# DoorLockShield.net
KiCad netlist of a schematic drawn in EAGLE
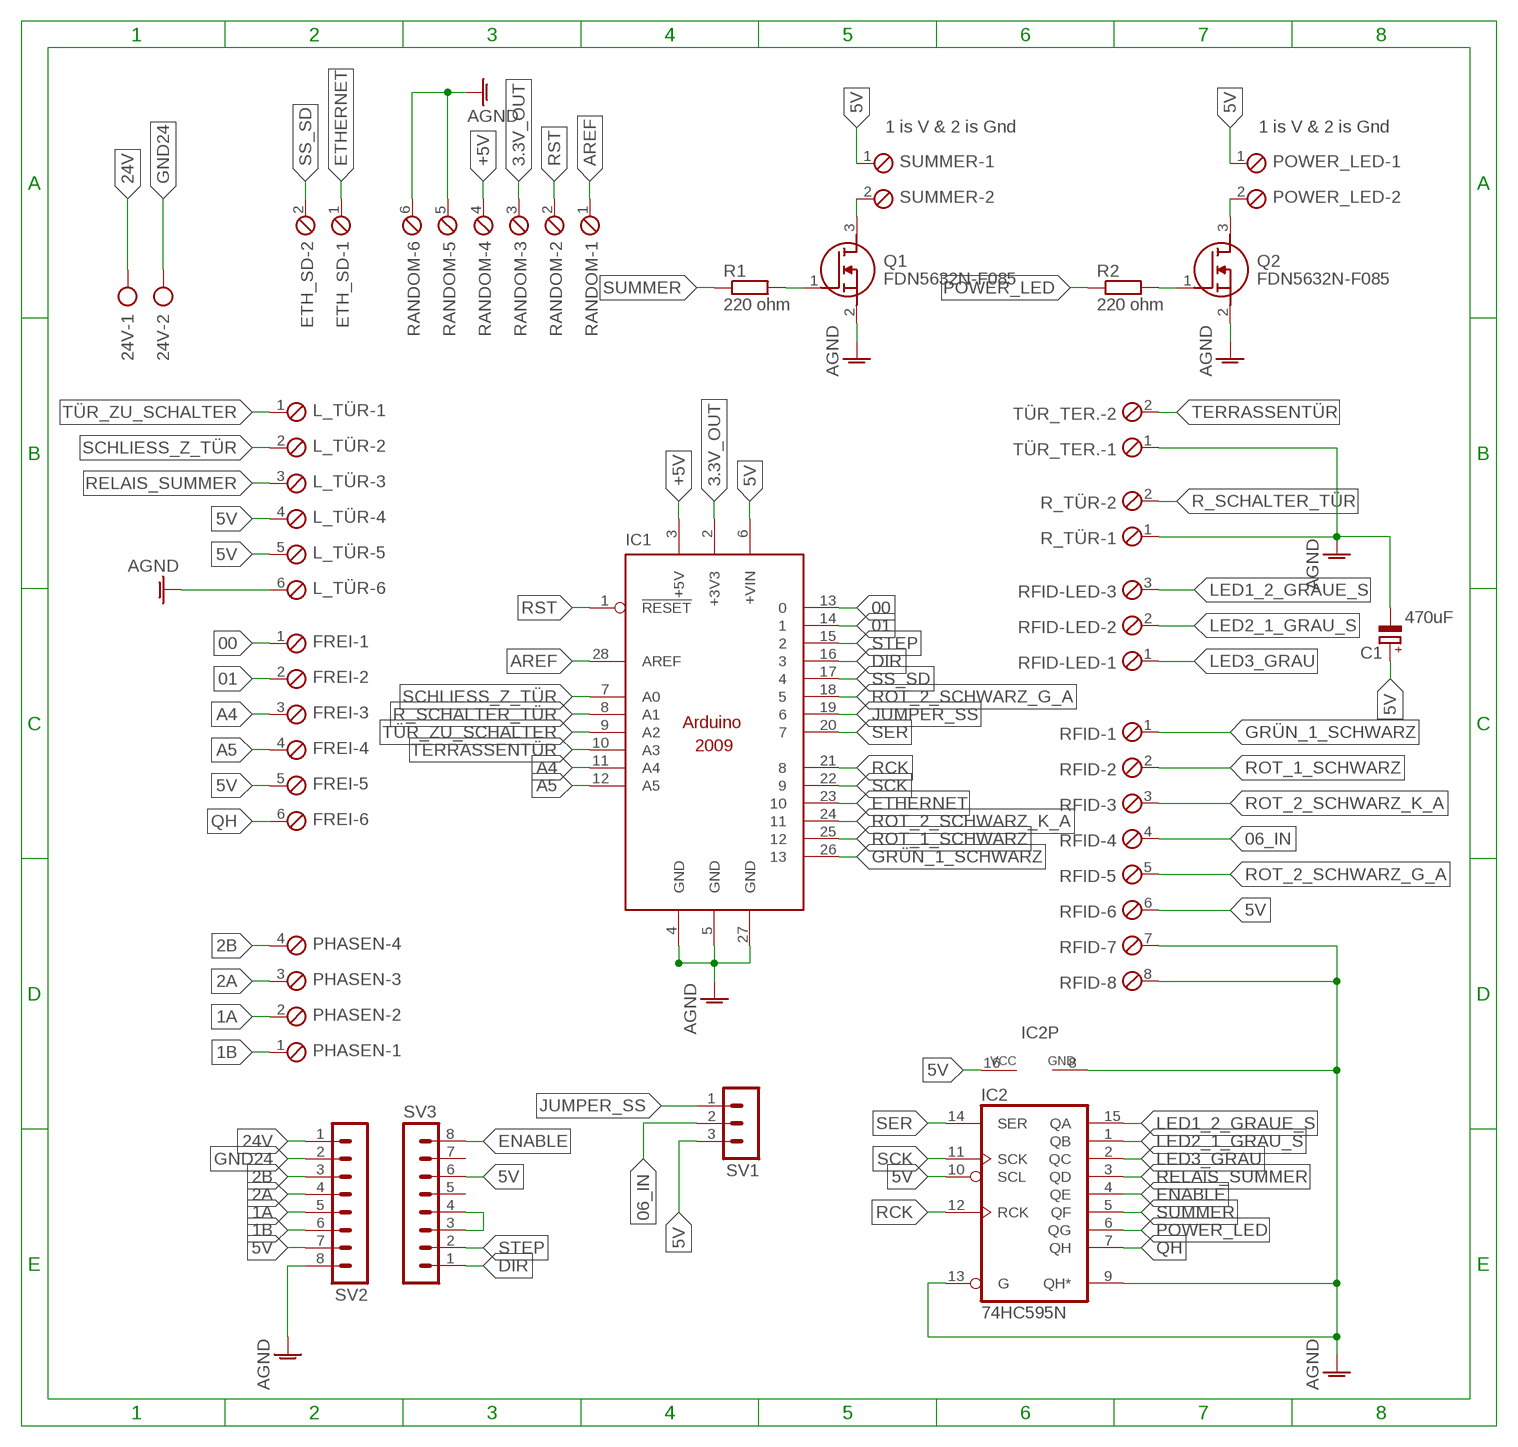
[diagram p0: schematic, sheet 1]

(export (version "E")
  (design (tool "Eeschema 10.0.6"))
  (components
    (comp (ref "24V")
      (value "AK500/2")
      (footprint "eagle-import:AK500_2")
      (libsource (lib "eagle-import") (part "AK500/2"))
    )
    (comp (ref "C1")
      (value "470uF")
      (footprint "eagle-import:E7,5-16")
      (libsource (lib "eagle-import") (part "CPOL-EUE7.5-16"))
    )
    (comp (ref "ETH_SD")
      (value "MPT2")
      (footprint "eagle-import:2POL254")
      (libsource (lib "eagle-import") (part "MPT2"))
    )
    (comp (ref "FREI")
      (value "MPT6")
      (footprint "eagle-import:6POL254")
      (libsource (lib "eagle-import") (part "MPT6"))
    )
    (comp (ref "IC1")
      (value "ARDUINO2009_12")
      (footprint "eagle-import:ARDUINO2009_2")
      (libsource (lib "eagle-import") (part "ARDUINO2009_12"))
    )
    (comp (ref "IC2")
      (value "74HC595N")
      (footprint "eagle-import:DIL16")
      (libsource (lib "eagle-import") (part "74595NHC"))
    )
    (comp (ref "L_TÜR")
      (value "MPT6")
      (footprint "eagle-import:6POL254")
      (libsource (lib "eagle-import") (part "MPT6"))
    )
    (comp (ref "PHASEN")
      (value "MPT4")
      (footprint "eagle-import:4POL254")
      (libsource (lib "eagle-import") (part "MPT4"))
    )
    (comp (ref "POWER_LED")
      (value "1 is V & 2 is Gnd")
      (footprint "eagle-import:2POL254")
      (libsource (lib "eagle-import") (part "MPT2"))
    )
    (comp (ref "Q1")
      (value "FDN5632N-F085")
      (footprint "eagle-import:SOT95P237X122-3N")
      (fields (field (name "MOUSER_PART_NUMBER") "512-FDN5632N-F085"))
      (libsource (lib "eagle-import") (part "FDN5632N-F085"))
    )
    (comp (ref "Q2")
      (value "FDN5632N-F085")
      (footprint "eagle-import:SOT95P237X122-3N")
      (fields (field (name "MOUSER_PART_NUMBER") "512-FDN5632N-F085"))
      (libsource (lib "eagle-import") (part "FDN5632N-F085"))
    )
    (comp (ref "R1")
      (value "220 ohm")
      (footprint "eagle-import:R0805")
      (libsource (lib "eagle-import") (part "R-EU_805R0805"))
    )
    (comp (ref "R2")
      (value "220 ohm")
      (footprint "eagle-import:R0805")
      (libsource (lib "eagle-import") (part "R-EU_805R0805"))
    )
    (comp (ref "RANDOM")
      (value "MPT6")
      (footprint "eagle-import:6POL254")
      (libsource (lib "eagle-import") (part "MPT6"))
    )
    (comp (ref "RFID")
      (value "MPT8")
      (footprint "eagle-import:8POL254")
      (libsource (lib "eagle-import") (part "MPT8"))
    )
    (comp (ref "RFID-LED")
      (value "MPT3")
      (footprint "eagle-import:3POL254")
      (libsource (lib "eagle-import") (part "MPT3"))
    )
    (comp (ref "R_TÜR")
      (value "MPT2")
      (footprint "eagle-import:2POL254")
      (libsource (lib "eagle-import") (part "MPT2"))
    )
    (comp (ref "SUMMER")
      (value "1 is V & 2 is Gnd")
      (footprint "eagle-import:2POL254")
      (libsource (lib "eagle-import") (part "MPT2"))
    )
    (comp (ref "SV1")
      (value "MA03-1")
      (footprint "eagle-import:MA03-1")
      (libsource (lib "eagle-import") (part "MA03-1"))
    )
    (comp (ref "SV2")
      (value "MA08-1")
      (footprint "eagle-import:MA08-1")
      (libsource (lib "eagle-import") (part "MA08-1"))
    )
    (comp (ref "SV3")
      (value "MA08-1")
      (footprint "eagle-import:MA08-1")
      (libsource (lib "eagle-import") (part "MA08-1"))
    )
    (comp (ref "TÜR_TER.")
      (value "MPT2")
      (footprint "eagle-import:2POL254")
      (libsource (lib "eagle-import") (part "MPT2"))
    )
  )
  (nets
    (net (code "1") (name "+5V") (class "Default")
      (node (ref "IC1") (pin "3") (pinfunction "+5V_3") (pintype "power_in"))
      (node (ref "RANDOM") (pin "4") (pinfunction "1_4") (pintype "passive"))
    )
    (net (code "2") (name "00") (class "Default")
      (node (ref "FREI") (pin "1") (pinfunction "1_1") (pintype "passive"))
      (node (ref "IC1") (pin "13") (pinfunction "0_13") (pintype "bidirectional"))
    )
    (net (code "3") (name "01") (class "Default")
      (node (ref "FREI") (pin "2") (pinfunction "1_2") (pintype "passive"))
      (node (ref "IC1") (pin "14") (pinfunction "1_14") (pintype "bidirectional"))
    )
    (net (code "4") (name "1A") (class "Default")
      (node (ref "PHASEN") (pin "2") (pinfunction "1_2") (pintype "passive"))
      (node (ref "SV2") (pin "5") (pinfunction "5_5") (pintype "passive"))
    )
    (net (code "5") (name "1B") (class "Default")
      (node (ref "PHASEN") (pin "1") (pinfunction "1_1") (pintype "passive"))
      (node (ref "SV2") (pin "6") (pinfunction "6_6") (pintype "passive"))
    )
    (net (code "6") (name "2A") (class "Default")
      (node (ref "PHASEN") (pin "3") (pinfunction "1_3") (pintype "passive"))
      (node (ref "SV2") (pin "4") (pinfunction "4_4") (pintype "passive"))
    )
    (net (code "7") (name "2B") (class "Default")
      (node (ref "PHASEN") (pin "4") (pinfunction "1_4") (pintype "passive"))
      (node (ref "SV2") (pin "3") (pinfunction "3_3") (pintype "passive"))
    )
    (net (code "8") (name "3.3V_OUT") (class "Default")
      (node (ref "IC1") (pin "2") (pinfunction "+3V3_2") (pintype "power_in"))
      (node (ref "RANDOM") (pin "3") (pinfunction "1_3") (pintype "passive"))
    )
    (net (code "9") (name "5V") (class "Default")
      (node (ref "C1") (pin "+") (pinfunction "+_+") (pintype "passive"))
      (node (ref "FREI") (pin "5") (pinfunction "1_5") (pintype "passive"))
      (node (ref "IC1") (pin "6") (pinfunction "+VIN_6") (pintype "bidirectional"))
      (node (ref "IC2") (pin "10") (pinfunction "SCL_10") (pintype "input"))
      (node (ref "IC2") (pin "16") (pinfunction "VCC_16") (pintype "power_in"))
      (node (ref "L_TÜR") (pin "4") (pinfunction "1_4") (pintype "passive"))
      (node (ref "L_TÜR") (pin "5") (pinfunction "1_5") (pintype "passive"))
      (node (ref "POWER_LED") (pin "1") (pinfunction "1_1") (pintype "passive"))
      (node (ref "RFID") (pin "6") (pinfunction "1_6") (pintype "passive"))
      (node (ref "SUMMER") (pin "1") (pinfunction "1_1") (pintype "passive"))
      (node (ref "SV1") (pin "3") (pinfunction "3_3") (pintype "passive"))
      (node (ref "SV2") (pin "7") (pinfunction "7_7") (pintype "passive"))
      (node (ref "SV3") (pin "6") (pinfunction "6_6") (pintype "passive"))
    )
    (net (code "10") (name "06_IN") (class "Default")
      (node (ref "RFID") (pin "4") (pinfunction "1_4") (pintype "passive"))
      (node (ref "SV1") (pin "2") (pinfunction "2_2") (pintype "passive"))
    )
    (net (code "11") (name "24V") (class "Default")
      (node (ref "24V") (pin "1") (pinfunction "KL_1") (pintype "passive"))
      (node (ref "SV2") (pin "1") (pinfunction "1_1") (pintype "passive"))
    )
    (net (code "12") (name "A4") (class "Default")
      (node (ref "FREI") (pin "3") (pinfunction "1_3") (pintype "passive"))
      (node (ref "IC1") (pin "11") (pinfunction "A4_11") (pintype "bidirectional"))
    )
    (net (code "13") (name "A5") (class "Default")
      (node (ref "FREI") (pin "4") (pinfunction "1_4") (pintype "passive"))
      (node (ref "IC1") (pin "12") (pinfunction "A5_12") (pintype "bidirectional"))
    )
    (net (code "14") (name "AGND") (class "Default")
      (node (ref "C1") (pin "-") (pinfunction "-_-") (pintype "passive"))
      (node (ref "IC1") (pin "27") (pinfunction "GND_27") (pintype "power_in"))
      (node (ref "IC1") (pin "4") (pinfunction "GND_4") (pintype "power_in"))
      (node (ref "IC1") (pin "5") (pinfunction "GND_5") (pintype "power_in"))
      (node (ref "IC2") (pin "13") (pinfunction "G_13") (pintype "input"))
      (node (ref "IC2") (pin "8") (pinfunction "GND_8") (pintype "power_in"))
      (node (ref "IC2") (pin "9") (pinfunction "QH*_9") (pintype "tri_state"))
      (node (ref "L_TÜR") (pin "6") (pinfunction "1_6") (pintype "passive"))
      (node (ref "Q1") (pin "2") (pinfunction "S_2") (pintype "bidirectional"))
      (node (ref "Q2") (pin "2") (pinfunction "S_2") (pintype "bidirectional"))
      (node (ref "RANDOM") (pin "5") (pinfunction "1_5") (pintype "passive"))
      (node (ref "RANDOM") (pin "6") (pinfunction "1_6") (pintype "passive"))
      (node (ref "RFID") (pin "7") (pinfunction "1_7") (pintype "passive"))
      (node (ref "RFID") (pin "8") (pinfunction "1_8") (pintype "passive"))
      (node (ref "R_TÜR") (pin "1") (pinfunction "1_1") (pintype "passive"))
      (node (ref "SV2") (pin "8") (pinfunction "8_8") (pintype "passive"))
      (node (ref "TÜR_TER.") (pin "1") (pinfunction "1_1") (pintype "passive"))
    )
    (net (code "15") (name "AREF") (class "Default")
      (node (ref "IC1") (pin "28") (pinfunction "AREF_28") (pintype "bidirectional"))
      (node (ref "RANDOM") (pin "1") (pinfunction "1_1") (pintype "passive"))
    )
    (net (code "16") (name "DIR") (class "Default")
      (node (ref "IC1") (pin "16") (pinfunction "3_16") (pintype "bidirectional"))
      (node (ref "SV3") (pin "1") (pinfunction "1_1") (pintype "passive"))
    )
    (net (code "17") (name "ENABLE") (class "Default")
      (node (ref "IC2") (pin "4") (pinfunction "QE_4") (pintype "tri_state"))
      (node (ref "SV3") (pin "8") (pinfunction "8_8") (pintype "passive"))
    )
    (net (code "18") (name "ETHERNET") (class "Default")
      (node (ref "ETH_SD") (pin "1") (pinfunction "1_1") (pintype "passive"))
      (node (ref "IC1") (pin "23") (pinfunction "10_23") (pintype "bidirectional"))
    )
    (net (code "19") (name "GND24") (class "Default")
      (node (ref "24V") (pin "2") (pinfunction "KL_2") (pintype "passive"))
      (node (ref "SV2") (pin "2") (pinfunction "2_2") (pintype "passive"))
    )
    (net (code "20") (name "GRÜN_1_SCHWARZ") (class "Default")
      (node (ref "IC1") (pin "26") (pinfunction "13_26") (pintype "bidirectional"))
      (node (ref "RFID") (pin "1") (pinfunction "1_1") (pintype "passive"))
    )
    (net (code "21") (name "JUMPER_SS") (class "Default")
      (node (ref "IC1") (pin "19") (pinfunction "6_19") (pintype "bidirectional"))
      (node (ref "SV1") (pin "1") (pinfunction "1_1") (pintype "passive"))
    )
    (net (code "22") (name "LED1_2_GRAUE_S") (class "Default")
      (node (ref "IC2") (pin "15") (pinfunction "QA_15") (pintype "tri_state"))
      (node (ref "RFID-LED") (pin "3") (pinfunction "1_3") (pintype "passive"))
    )
    (net (code "23") (name "LED2_1_GRAU_S") (class "Default")
      (node (ref "IC2") (pin "1") (pinfunction "QB_1") (pintype "tri_state"))
      (node (ref "RFID-LED") (pin "2") (pinfunction "1_2") (pintype "passive"))
    )
    (net (code "24") (name "LED3_GRAU") (class "Default")
      (node (ref "IC2") (pin "2") (pinfunction "QC_2") (pintype "tri_state"))
      (node (ref "RFID-LED") (pin "1") (pinfunction "1_1") (pintype "passive"))
    )
    (net (code "25") (name "Net-(POWER_LEDB-1)") (class "Default")
      (node (ref "POWER_LED") (pin "2") (pinfunction "1_2") (pintype "passive"))
      (node (ref "Q2") (pin "3") (pinfunction "D_3") (pintype "bidirectional"))
    )
    (net (code "26") (name "Net-(Q1-D)") (class "Default")
      (node (ref "Q1") (pin "3") (pinfunction "D_3") (pintype "bidirectional"))
      (node (ref "SUMMER") (pin "2") (pinfunction "1_2") (pintype "passive"))
    )
    (net (code "27") (name "Net-(Q1-G)") (class "Default")
      (node (ref "Q1") (pin "1") (pinfunction "G_1") (pintype "bidirectional"))
      (node (ref "R1") (pin "2") (pinfunction "2_2") (pintype "passive"))
    )
    (net (code "28") (name "Net-(Q2-G)") (class "Default")
      (node (ref "Q2") (pin "1") (pinfunction "G_1") (pintype "bidirectional"))
      (node (ref "R2") (pin "2") (pinfunction "2_2") (pintype "passive"))
    )
    (net (code "29") (name "Net-(SV3-Pad3)") (class "Default")
      (node (ref "SV3") (pin "3") (pinfunction "3_3") (pintype "passive"))
      (node (ref "SV3") (pin "4") (pinfunction "4_4") (pintype "passive"))
    )
    (net (code "30") (name "POWER_LED") (class "Default")
      (node (ref "IC2") (pin "6") (pinfunction "QG_6") (pintype "tri_state"))
      (node (ref "R2") (pin "1") (pinfunction "1_1") (pintype "passive"))
    )
    (net (code "31") (name "QH") (class "Default")
      (node (ref "FREI") (pin "6") (pinfunction "1_6") (pintype "passive"))
      (node (ref "IC2") (pin "7") (pinfunction "QH_7") (pintype "tri_state"))
    )
    (net (code "32") (name "RCK") (class "Default")
      (node (ref "IC1") (pin "21") (pinfunction "8_21") (pintype "bidirectional"))
      (node (ref "IC2") (pin "12") (pinfunction "RCK_12") (pintype "input"))
    )
    (net (code "33") (name "RELAIS_SUMMER") (class "Default")
      (node (ref "IC2") (pin "3") (pinfunction "QD_3") (pintype "tri_state"))
      (node (ref "L_TÜR") (pin "3") (pinfunction "1_3") (pintype "passive"))
    )
    (net (code "34") (name "ROT_1_SCHWARZ") (class "Default")
      (node (ref "IC1") (pin "25") (pinfunction "12_25") (pintype "bidirectional"))
      (node (ref "RFID") (pin "2") (pinfunction "1_2") (pintype "passive"))
    )
    (net (code "35") (name "ROT_2_SCHWARZ_G_A") (class "Default")
      (node (ref "IC1") (pin "18") (pinfunction "5_18") (pintype "bidirectional"))
      (node (ref "RFID") (pin "5") (pinfunction "1_5") (pintype "passive"))
    )
    (net (code "36") (name "ROT_2_SCHWARZ_K_A") (class "Default")
      (node (ref "IC1") (pin "24") (pinfunction "11_24") (pintype "bidirectional"))
      (node (ref "RFID") (pin "3") (pinfunction "1_3") (pintype "passive"))
    )
    (net (code "37") (name "RST") (class "Default")
      (node (ref "IC1") (pin "1") (pinfunction "~{RESET}_1") (pintype "bidirectional"))
      (node (ref "RANDOM") (pin "2") (pinfunction "1_2") (pintype "passive"))
    )
    (net (code "38") (name "R_SCHALTER_TÜR") (class "Default")
      (node (ref "IC1") (pin "8") (pinfunction "A1_8") (pintype "bidirectional"))
      (node (ref "R_TÜR") (pin "2") (pinfunction "1_2") (pintype "passive"))
    )
    (net (code "39") (name "SCHLIESS_Z_TÜR") (class "Default")
      (node (ref "IC1") (pin "7") (pinfunction "A0_7") (pintype "bidirectional"))
      (node (ref "L_TÜR") (pin "2") (pinfunction "1_2") (pintype "passive"))
    )
    (net (code "40") (name "SCK") (class "Default")
      (node (ref "IC1") (pin "22") (pinfunction "9_22") (pintype "bidirectional"))
      (node (ref "IC2") (pin "11") (pinfunction "SCK_11") (pintype "input"))
    )
    (net (code "41") (name "SER") (class "Default")
      (node (ref "IC1") (pin "20") (pinfunction "7_20") (pintype "bidirectional"))
      (node (ref "IC2") (pin "14") (pinfunction "SER_14") (pintype "input"))
    )
    (net (code "42") (name "SS_SD") (class "Default")
      (node (ref "ETH_SD") (pin "2") (pinfunction "1_2") (pintype "passive"))
      (node (ref "IC1") (pin "17") (pinfunction "4_17") (pintype "bidirectional"))
    )
    (net (code "43") (name "STEP") (class "Default")
      (node (ref "IC1") (pin "15") (pinfunction "2_15") (pintype "bidirectional"))
      (node (ref "SV3") (pin "2") (pinfunction "2_2") (pintype "passive"))
    )
    (net (code "44") (name "SUMMER") (class "Default")
      (node (ref "IC2") (pin "5") (pinfunction "QF_5") (pintype "tri_state"))
      (node (ref "R1") (pin "1") (pinfunction "1_1") (pintype "passive"))
    )
    (net (code "45") (name "TERRASSENTÜR") (class "Default")
      (node (ref "IC1") (pin "10") (pinfunction "A3_10") (pintype "bidirectional"))
      (node (ref "TÜR_TER.") (pin "2") (pinfunction "1_2") (pintype "passive"))
    )
    (net (code "46") (name "TÜR_ZU_SCHALTER") (class "Default")
      (node (ref "IC1") (pin "9") (pinfunction "A2_9") (pintype "bidirectional"))
      (node (ref "L_TÜR") (pin "1") (pinfunction "1_1") (pintype "passive"))
    )
    (net (code "47") (name "unconnected-(SV3-Pad5)") (class "Default")
      (node (ref "SV3") (pin "5") (pinfunction "5_5") (pintype "passive"))
    )
    (net (code "48") (name "unconnected-(SV3-Pad7)") (class "Default")
      (node (ref "SV3") (pin "7") (pinfunction "7_7") (pintype "passive"))
    )
  )
)
